# SCH_Firefly_v0_1_2025-03-03.net
KiCad netlist of a schematic drawn in EasyEDA
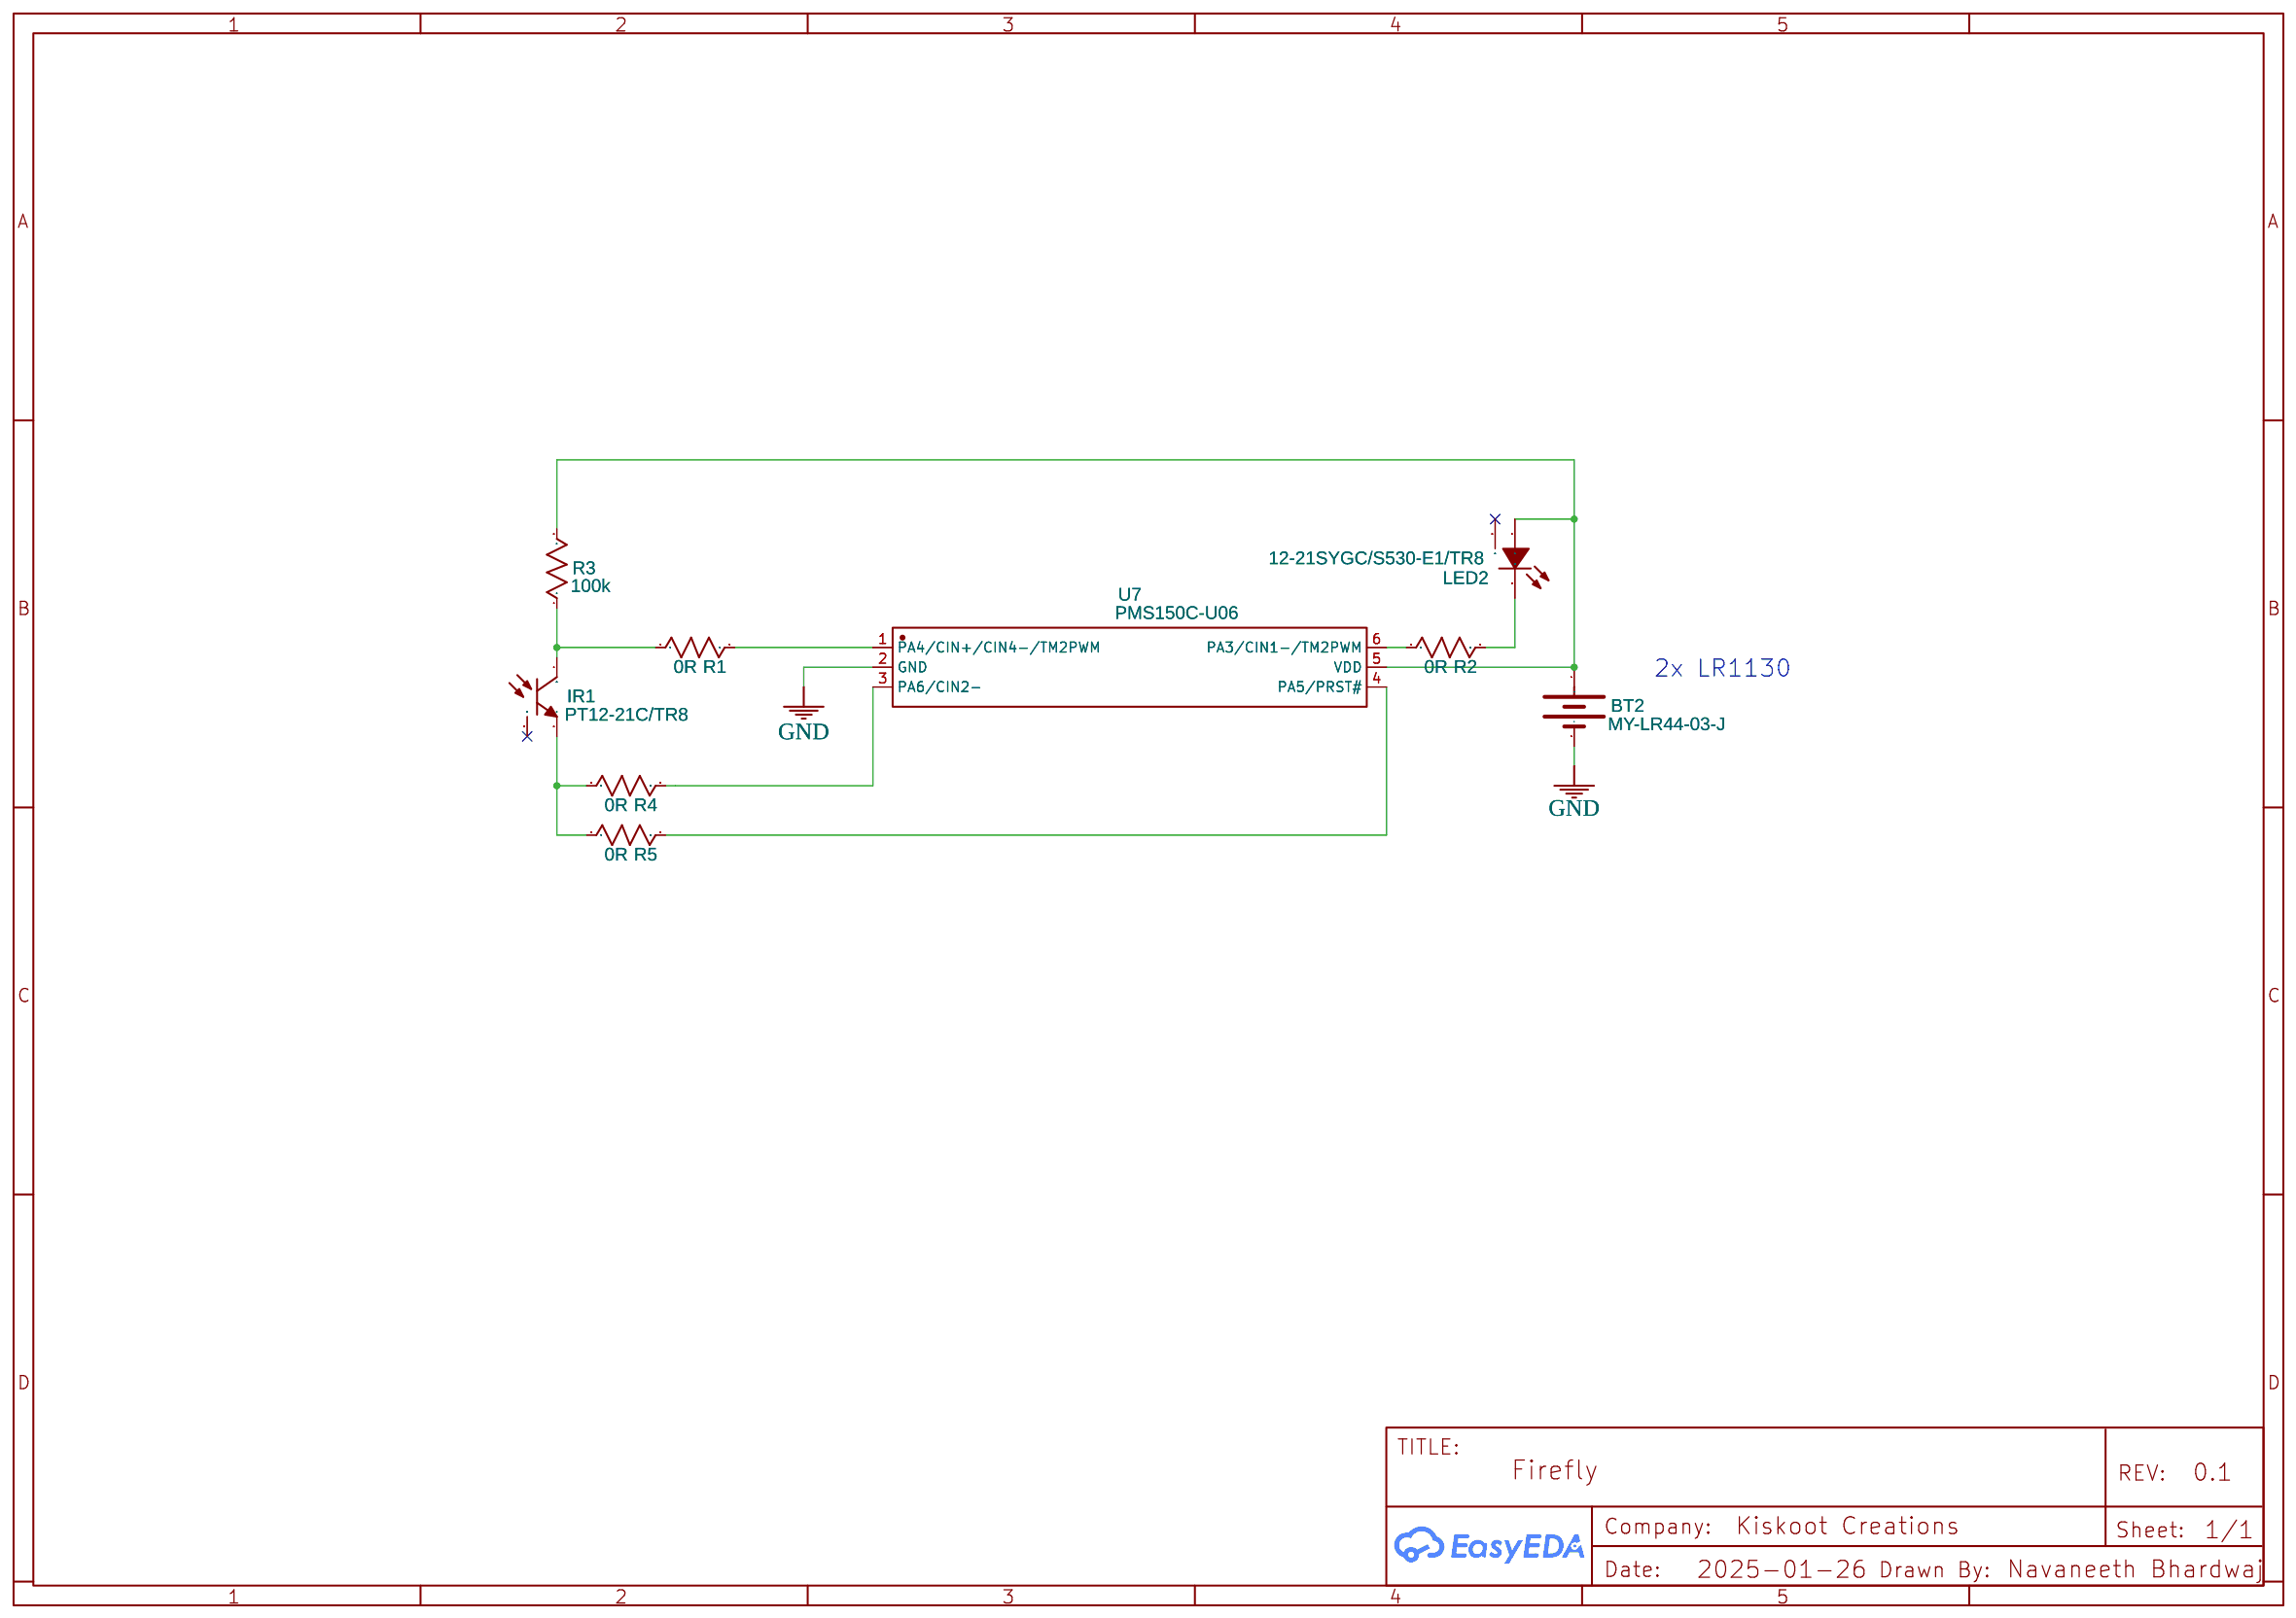
[diagram p0: schematic sheet]

(export (version "E")
  (design (tool "Eeschema 10.0.6"))
  (components
    (comp (ref "BT2")
      (value "MY-LR44-03-J")
      (fields (field (name "Manufacturer") "MYOUNG(美阳)"))
      (libsource (lib "") (part "MY-LR44-03-J"))
    )
    (comp (ref "IR1")
      (value "PT12-21C/TR8")
      (fields (field (name "Manufacturer") "EVERLIGHT(亿光)"))
      (libsource (lib "") (part "PT12-21C/TR8"))
    )
    (comp (ref "LED2")
      (value "12-21SYGC/S530-E1/TR8")
      (fields (field (name "Manufacturer") "EVERLIGHT(亿光)"))
      (libsource (lib "") (part "12-21SYGC/S530-E1/TR8"))
    )
    (comp (ref "R1") (value "0R") (libsource (lib "") (part "R_0603_US")))
    (comp (ref "R2") (value "0R") (libsource (lib "") (part "R_0603_US")))
    (comp (ref "R3") (value "100k") (libsource (lib "") (part "R_0603_US_1")))
    (comp (ref "R4") (value "0R") (libsource (lib "") (part "R_0603_US")))
    (comp (ref "R5") (value "0R") (libsource (lib "") (part "R_0603_US")))
    (comp (ref "U7")
      (value "PMS150C-U06")
      (fields (field (name "Manufacturer") "PADAUK(应广)"))
      (libsource (lib "") (part "PMS150C-U06"))
    )
  )
  (nets
    (net (code "1") (name "GND") (class "Default")
      (node (ref "BT2") (pin "2") (pinfunction "-_2") (pintype "passive"))
      (node (ref "U7") (pin "2") (pinfunction "GND_2") (pintype "unspecified"))
    )
    (net (code "2") (name "Net-(BT2-+)") (class "Default")
      (node (ref "BT2") (pin "1") (pinfunction "+_1") (pintype "passive"))
      (node (ref "LED2") (pin "1") (pinfunction "A_1") (pintype "unspecified"))
      (node (ref "R3") (pin "2") (pinfunction "2_2") (pintype "unspecified"))
      (node (ref "U7") (pin "5") (pinfunction "VDD_5") (pintype "unspecified"))
    )
    (net (code "3") (name "Net-(IR1-C)") (class "Default")
      (node (ref "IR1") (pin "1") (pinfunction "C_1") (pintype "input"))
      (node (ref "R1") (pin "1") (pinfunction "1_1") (pintype "unspecified"))
      (node (ref "R3") (pin "1") (pinfunction "1_1") (pintype "unspecified"))
    )
    (net (code "4") (name "Net-(IR1-E)") (class "Default")
      (node (ref "IR1") (pin "2") (pinfunction "E_2") (pintype "input"))
      (node (ref "R4") (pin "1") (pinfunction "1_1") (pintype "unspecified"))
      (node (ref "R5") (pin "1") (pinfunction "1_1") (pintype "unspecified"))
    )
    (net (code "5") (name "Net-(LED2-C)") (class "Default")
      (node (ref "LED2") (pin "2") (pinfunction "C_2") (pintype "unspecified"))
      (node (ref "R2") (pin "2") (pinfunction "2_2") (pintype "unspecified"))
    )
    (net (code "6") (name "Net-(U7-PA3{slash}CIN1-{slash}TM2PWM)") (class "Default")
      (node (ref "R2") (pin "1") (pinfunction "1_1") (pintype "unspecified"))
      (node (ref "U7") (pin "6") (pinfunction "PA3/CIN1-/TM2PWM_6") (pintype "unspecified"))
    )
    (net (code "7") (name "Net-(U7-PA4{slash}CIN+{slash}CIN4-{slash}TM2PWM)") (class "Default")
      (node (ref "R1") (pin "2") (pinfunction "2_2") (pintype "unspecified"))
      (node (ref "U7") (pin "1") (pinfunction "PA4/CIN+/CIN4-/TM2PWM_1") (pintype "unspecified"))
    )
    (net (code "8") (name "Net-(U7-PA5{slash}PRST#)") (class "Default")
      (node (ref "R5") (pin "2") (pinfunction "2_2") (pintype "unspecified"))
      (node (ref "U7") (pin "4") (pinfunction "PA5/PRST#_4") (pintype "unspecified"))
    )
    (net (code "9") (name "Net-(U7-PA6{slash}CIN2-)") (class "Default")
      (node (ref "R4") (pin "2") (pinfunction "2_2") (pintype "unspecified"))
      (node (ref "U7") (pin "3") (pinfunction "PA6/CIN2-_3") (pintype "unspecified"))
    )
    (net (code "10") (name "unconnected-(IR1-Pad3)") (class "Default")
      (node (ref "IR1") (pin "3") (pinfunction "3_3") (pintype "input+no_connect"))
    )
    (net (code "11") (name "unconnected-(LED2-Pad3)") (class "Default")
      (node (ref "LED2") (pin "3") (pinfunction "3_3") (pintype "unspecified+no_connect"))
    )
  )
)
